# flyback.net
KiCad netlist of a schematic drawn in EAGLE
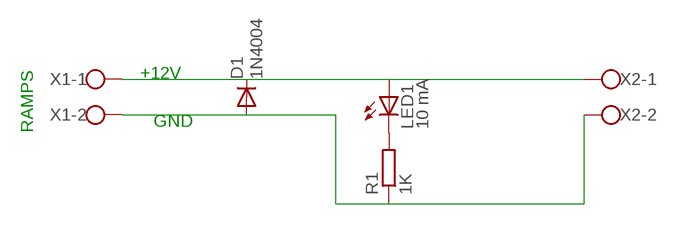
[diagram p0: schematic, sheet 1]

(export (version "E")
  (design (tool "Eeschema 10.0.6"))
  (components
    (comp (ref "D1")
      (value "1N4004")
      (footprint "eagle-import:DO41-10")
      (libsource (lib "eagle-import") (part "1N4004"))
    )
    (comp (ref "LED1")
      (value "10 mA")
      (footprint "eagle-import:LED3MM")
      (libsource (lib "eagle-import") (part "LED3MM"))
    )
    (comp (ref "R1")
      (value "1K")
      (footprint "eagle-import:P0817_22")
      (libsource (lib "eagle-import") (part "R-EU_0817/22"))
    )
    (comp (ref "X1")
      (value "W237-102")
      (footprint "eagle-import:W237-102")
      (fields (field (name "MPN") "237-102"))
      (libsource (lib "eagle-import") (part "W237-102"))
    )
    (comp (ref "X2")
      (value "W237-102")
      (footprint "eagle-import:W237-102")
      (fields (field (name "MPN") "237-102"))
      (libsource (lib "eagle-import") (part "W237-102"))
    )
  )
  (nets
    (net (code "1") (name "Net-(LED1-C)") (class "Default")
      (node (ref "LED1") (pin "K") (pinfunction "C_K") (pintype "passive"))
      (node (ref "R1") (pin "2") (pinfunction "2_2") (pintype "passive"))
    )
    (net (code "2") (name "Net-(X1A-KL)") (class "Default")
      (node (ref "D1") (pin "C") (pinfunction "C_C") (pintype "passive"))
      (node (ref "X1") (pin "1") (pinfunction "KL_1") (pintype "passive"))
      (node (ref "X2") (pin "1") (pinfunction "KL_1") (pintype "passive"))
    )
    (net (code "3") (name "Net-(X1B-KL)") (class "Default")
      (node (ref "D1") (pin "A") (pinfunction "A_A") (pintype "passive"))
      (node (ref "R1") (pin "1") (pinfunction "1_1") (pintype "passive"))
      (node (ref "X1") (pin "2") (pinfunction "KL_2") (pintype "passive"))
      (node (ref "X2") (pin "2") (pinfunction "KL_2") (pintype "passive"))
    )
    (net (code "4") (name "unconnected-(LED1-PadA)") (class "Default")
      (node (ref "LED1") (pin "A") (pinfunction "A_A") (pintype "passive"))
    )
  )
)
